# CW308T_K24_Misc.net
KiCad netlist of a schematic drawn in Altium Designer
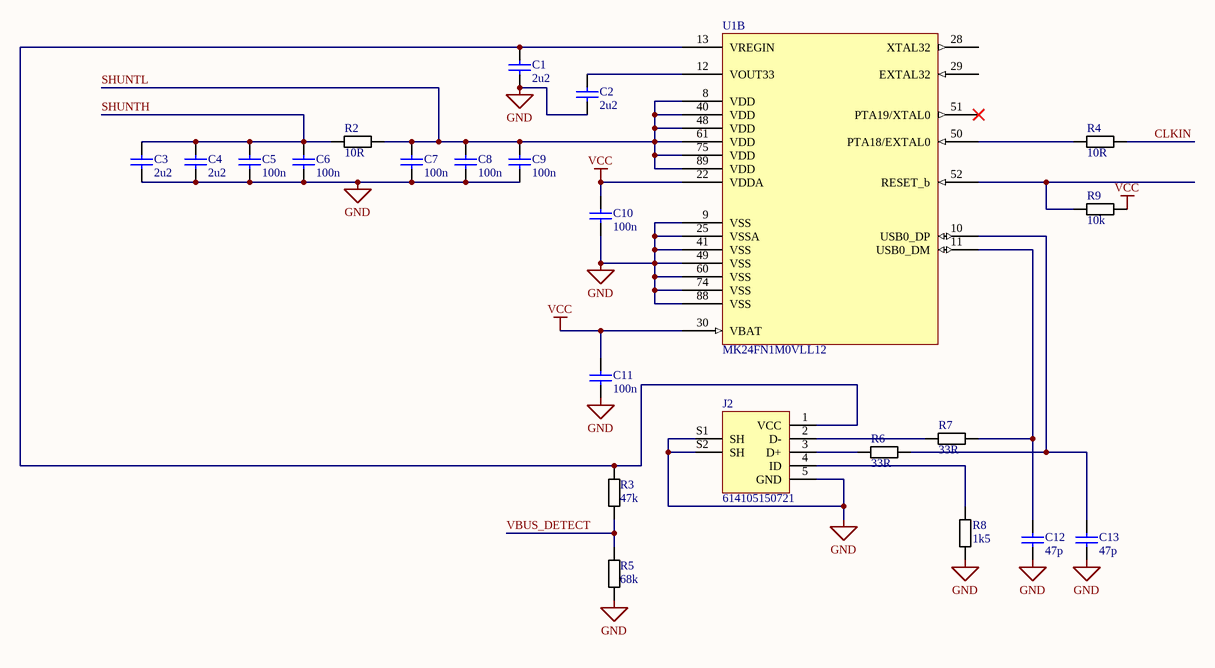
[diagram p0: CW308T_K24_Misc.SchDoc]

(export (version "E")
  (design (tool "Eeschema 10.0.6"))
  (components
    (comp (ref "C1")
      (value "2u2")
      (footprint "CAPC0603_M")
      (description "2u2, 0603")
      (fields (field (name "PART NUMBER") "CCHIP-2u2-0603"))
      (libsource (lib "NewAE_AltiumLib") (part "CAP"))
    )
    (comp (ref "C2")
      (value "2u2")
      (footprint "CAPC0603_M")
      (description "2u2, 0603")
      (fields (field (name "PART NUMBER") "CCHIP-2u2-0603"))
      (libsource (lib "NewAE_AltiumLib") (part "CAP"))
    )
    (comp (ref "C3")
      (value "2u2")
      (footprint "CAPC0603_M")
      (description "2u2, 0603")
      (fields (field (name "PART NUMBER") "CCHIP-2u2-0603"))
      (libsource (lib "NewAE_AltiumLib") (part "CAP"))
    )
    (comp (ref "C4")
      (value "2u2")
      (footprint "CAPC0603_M")
      (description "2u2, 0603")
      (fields (field (name "PART NUMBER") "CCHIP-2u2-0603"))
      (libsource (lib "NewAE_AltiumLib") (part "CAP"))
    )
    (comp (ref "C5")
      (value "100n")
      (footprint "CAPC0603_M")
      (description "100n, 0603")
      (fields (field (name "PART NUMBER") "CCHIP-100n-0603"))
      (libsource (lib "NewAE_AltiumLib") (part "CAP"))
    )
    (comp (ref "C6")
      (value "100n")
      (footprint "CAPC0603_M")
      (description "100n, 0603")
      (fields (field (name "PART NUMBER") "CCHIP-100n-0603"))
      (libsource (lib "NewAE_AltiumLib") (part "CAP"))
    )
    (comp (ref "C7")
      (value "100n")
      (footprint "CAPC0603_M")
      (description "100n, 0603")
      (fields (field (name "PART NUMBER") "CCHIP-100n-0603"))
      (libsource (lib "NewAE_AltiumLib") (part "CAP"))
    )
    (comp (ref "C8")
      (value "100n")
      (footprint "CAPC0603_M")
      (description "100n, 0603")
      (fields (field (name "PART NUMBER") "CCHIP-100n-0603"))
      (libsource (lib "NewAE_AltiumLib") (part "CAP"))
    )
    (comp (ref "C9")
      (value "100n")
      (footprint "CAPC0603_M")
      (description "100n, 0603")
      (fields (field (name "PART NUMBER") "CCHIP-100n-0603"))
      (libsource (lib "NewAE_AltiumLib") (part "CAP"))
    )
    (comp (ref "C10")
      (value "100n")
      (footprint "CAPC0603_M")
      (description "100n, 0603")
      (fields (field (name "PART NUMBER") "CCHIP-100n-0603"))
      (libsource (lib "NewAE_AltiumLib") (part "CAP"))
    )
    (comp (ref "C11")
      (value "100n")
      (footprint "CAPC0603_M")
      (description "100n, 0603")
      (fields (field (name "PART NUMBER") "CCHIP-100n-0603"))
      (libsource (lib "NewAE_AltiumLib") (part "CAP"))
    )
    (comp (ref "C12")
      (value "47p")
      (footprint "CAPC0603_M")
      (description "47p, 0603")
      (fields (field (name "PART NUMBER") "CCHIP-47p-0603"))
      (libsource (lib "NewAE_AltiumLib") (part "CAP"))
    )
    (comp (ref "C13")
      (value "47p")
      (footprint "CAPC0603_M")
      (description "47p, 0603")
      (fields (field (name "PART NUMBER") "CCHIP-47p-0603"))
      (libsource (lib "NewAE_AltiumLib") (part "CAP"))
    )
    (comp (ref "J2")
      (value "614105150721")
      (footprint "614105150721")
      (description "USB, 5-pin, Upright")
      (libsource (lib "NewAE_AltiumLib") (part "USB_5PIN_2SHIELD"))
    )
    (comp (ref "R2")
      (value "10R")
      (footprint "RESC1608X55N")
      (description "10R res, 0603, 1%, 1/10W")
      (fields (field (name "PART NUMBER") "RCHIP-10R-0603") (field (name "TOLERANCE") "1%"))
      (libsource (lib "") (part "RES-EU_1"))
    )
    (comp (ref "R3")
      (value "47k")
      (footprint "RESC1608X55N")
      (description "47k res, 0603, 1%, 1/10W")
      (fields (field (name "PART NUMBER") "RCHIP-47K-0603") (field (name "TOLERANCE") "1%"))
      (libsource (lib "NewAE_AltiumLib") (part "RES-EU"))
    )
    (comp (ref "R4")
      (value "10R")
      (footprint "RESC1608X55N")
      (description "10R res, 0603, 1%, 1/10W")
      (fields (field (name "PART NUMBER") "RCHIP-10R-0603") (field (name "TOLERANCE") "1%"))
      (libsource (lib "") (part "RES-EU_1"))
    )
    (comp (ref "R5")
      (value "68k")
      (footprint "RESC1608X55N")
      (description "68k res, 0603, 1%, 1/10W")
      (fields (field (name "PART NUMBER") "RCHIP-68K-0603") (field (name "TOLERANCE") "1%"))
      (libsource (lib "NewAE_AltiumLib") (part "RES-EU"))
    )
    (comp (ref "R6")
      (value "33R")
      (footprint "RESC1608X55N")
      (description "33R res, 0603, 1%, 1/10W")
      (fields (field (name "PART NUMBER") "RCHIP-33R-0603") (field (name "TOLERANCE") "1%"))
      (libsource (lib "") (part "RES-EU_2"))
    )
    (comp (ref "R7")
      (value "33R")
      (footprint "RESC1608X55N")
      (description "33R res, 0603, 1%, 1/10W")
      (fields (field (name "PART NUMBER") "RCHIP-33R-0603") (field (name "TOLERANCE") "1%"))
      (libsource (lib "") (part "RES-EU_1"))
    )
    (comp (ref "R8")
      (value "1k5")
      (footprint "RESC1608X55N")
      (description "1k5 res, 0603, 1%, 1/10W")
      (fields (field (name "PART NUMBER") "RCHIP-1K5-0603") (field (name "TOLERANCE") "1%"))
      (libsource (lib "NewAE_AltiumLib") (part "RES-EU"))
    )
    (comp (ref "R9")
      (value "10k")
      (footprint "RESC1608X55N")
      (description "10k res, 0603, 1%, 1/10W")
      (fields (field (name "PART NUMBER") "RCHIP-10K-0603") (field (name "TOLERANCE") "1%"))
      (libsource (lib "") (part "RES-EU_1"))
    )
    (comp (ref "U1")
      (value "MK24FN1M0VLL12")
      (footprint "SQFP50P1600X1600X170-100N")
      (libsource (lib "NewAE_AltiumLib") (part "MK24FN1M0VLL12"))
    )
  )
  (nets
    (net (code "1") (name "/CLKIN") (class "Default")
      (node (ref "R4") (pin "2") (pinfunction "2_2") (pintype "passive"))
    )
    (net (code "2") (name "/SHUNTH") (class "Default")
      (node (ref "C3") (pin "1") (pinfunction "1_1") (pintype "passive"))
      (node (ref "C4") (pin "1") (pinfunction "1_1") (pintype "passive"))
      (node (ref "C5") (pin "1") (pinfunction "1_1") (pintype "passive"))
      (node (ref "C6") (pin "1") (pinfunction "1_1") (pintype "passive"))
      (node (ref "R2") (pin "1") (pinfunction "1_1") (pintype "passive"))
    )
    (net (code "3") (name "/SHUNTL") (class "Default")
      (node (ref "C7") (pin "1") (pinfunction "1_1") (pintype "passive"))
      (node (ref "C8") (pin "1") (pinfunction "1_1") (pintype "passive"))
      (node (ref "C9") (pin "1") (pinfunction "1_1") (pintype "passive"))
      (node (ref "R2") (pin "2") (pinfunction "2_2") (pintype "passive"))
      (node (ref "U1") (pin "40") (pinfunction "VDD_40") (pintype "power_in"))
      (node (ref "U1") (pin "48") (pinfunction "VDD_48") (pintype "power_in"))
      (node (ref "U1") (pin "61") (pinfunction "VDD_61") (pintype "power_in"))
      (node (ref "U1") (pin "75") (pinfunction "VDD_75") (pintype "power_in"))
      (node (ref "U1") (pin "8") (pinfunction "VDD_8") (pintype "power_in"))
      (node (ref "U1") (pin "89") (pinfunction "VDD_89") (pintype "power_in"))
    )
    (net (code "4") (name "/VBUS_DETECT") (class "Default")
      (node (ref "R3") (pin "2") (pinfunction "2_2") (pintype "passive"))
      (node (ref "R5") (pin "1") (pinfunction "1_1") (pintype "passive"))
    )
    (net (code "5") (name "GND") (class "Default")
      (node (ref "C1") (pin "2") (pinfunction "2_2") (pintype "passive"))
      (node (ref "C10") (pin "2") (pinfunction "2_2") (pintype "passive"))
      (node (ref "C11") (pin "2") (pinfunction "2_2") (pintype "passive"))
      (node (ref "C12") (pin "2") (pinfunction "2_2") (pintype "passive"))
      (node (ref "C13") (pin "2") (pinfunction "2_2") (pintype "passive"))
      (node (ref "C2") (pin "2") (pinfunction "2_2") (pintype "passive"))
      (node (ref "C3") (pin "2") (pinfunction "2_2") (pintype "passive"))
      (node (ref "C4") (pin "2") (pinfunction "2_2") (pintype "passive"))
      (node (ref "C5") (pin "2") (pinfunction "2_2") (pintype "passive"))
      (node (ref "C6") (pin "2") (pinfunction "2_2") (pintype "passive"))
      (node (ref "C7") (pin "2") (pinfunction "2_2") (pintype "passive"))
      (node (ref "C8") (pin "2") (pinfunction "2_2") (pintype "passive"))
      (node (ref "C9") (pin "2") (pinfunction "2_2") (pintype "passive"))
      (node (ref "J2") (pin "5") (pinfunction "GND_5") (pintype "power_in"))
      (node (ref "J2") (pin "S1") (pinfunction "SH_S1") (pintype "passive"))
      (node (ref "J2") (pin "S2") (pinfunction "SH_S2") (pintype "passive"))
      (node (ref "R5") (pin "2") (pinfunction "2_2") (pintype "passive"))
      (node (ref "R8") (pin "2") (pinfunction "2_2") (pintype "passive"))
      (node (ref "U1") (pin "25") (pinfunction "VSSA_25") (pintype "power_in"))
      (node (ref "U1") (pin "41") (pinfunction "VSS_41") (pintype "power_in"))
      (node (ref "U1") (pin "49") (pinfunction "VSS_49") (pintype "power_in"))
      (node (ref "U1") (pin "60") (pinfunction "VSS_60") (pintype "power_in"))
      (node (ref "U1") (pin "74") (pinfunction "VSS_74") (pintype "power_in"))
      (node (ref "U1") (pin "88") (pinfunction "VSS_88") (pintype "power_in"))
      (node (ref "U1") (pin "9") (pinfunction "VSS_9") (pintype "power_in"))
    )
    (net (code "6") (name "Net-(J2-D+)") (class "Default")
      (node (ref "J2") (pin "3") (pinfunction "D+_3") (pintype "passive"))
      (node (ref "R6") (pin "2") (pinfunction "2_2") (pintype "passive"))
    )
    (net (code "7") (name "Net-(J2-D-)") (class "Default")
      (node (ref "J2") (pin "2") (pinfunction "D-_2") (pintype "passive"))
      (node (ref "R7") (pin "1") (pinfunction "1_1") (pintype "passive"))
    )
    (net (code "8") (name "Net-(J2-ID)") (class "Default")
      (node (ref "J2") (pin "4") (pinfunction "ID_4") (pintype "power_in"))
      (node (ref "R8") (pin "1") (pinfunction "1_1") (pintype "passive"))
    )
    (net (code "9") (name "Net-(J2-VCC)") (class "Default")
      (node (ref "C1") (pin "1") (pinfunction "1_1") (pintype "passive"))
      (node (ref "J2") (pin "1") (pinfunction "VCC_1") (pintype "passive"))
      (node (ref "R3") (pin "1") (pinfunction "1_1") (pintype "passive"))
      (node (ref "U1") (pin "13") (pinfunction "VREGIN_13") (pintype "power_in"))
    )
    (net (code "10") (name "Net-(U1B-PTA18{slash}EXTAL0)") (class "Default")
      (node (ref "R4") (pin "1") (pinfunction "1_1") (pintype "passive"))
      (node (ref "U1") (pin "50") (pinfunction "PTA18/EXTAL0_50") (pintype "input"))
    )
    (net (code "11") (name "Net-(U1B-RESET_b)") (class "Default")
      (node (ref "R9") (pin "1") (pinfunction "1_1") (pintype "passive"))
      (node (ref "U1") (pin "52") (pinfunction "RESET_b_52") (pintype "input"))
    )
    (net (code "12") (name "Net-(U1B-USB0_DM)") (class "Default")
      (node (ref "C12") (pin "1") (pinfunction "1_1") (pintype "passive"))
      (node (ref "R7") (pin "2") (pinfunction "2_2") (pintype "passive"))
      (node (ref "U1") (pin "11") (pinfunction "USB0_DM_11") (pintype "bidirectional"))
    )
    (net (code "13") (name "Net-(U1B-USB0_DP)") (class "Default")
      (node (ref "C13") (pin "1") (pinfunction "1_1") (pintype "passive"))
      (node (ref "R6") (pin "1") (pinfunction "1_1") (pintype "passive"))
      (node (ref "U1") (pin "10") (pinfunction "USB0_DP_10") (pintype "bidirectional"))
    )
    (net (code "14") (name "Net-(U1B-VOUT33)") (class "Default")
      (node (ref "C2") (pin "1") (pinfunction "1_1") (pintype "passive"))
      (node (ref "U1") (pin "12") (pinfunction "VOUT33_12") (pintype "power_in"))
    )
    (net (code "15") (name "VCC") (class "Default")
      (node (ref "C10") (pin "1") (pinfunction "1_1") (pintype "passive"))
      (node (ref "C11") (pin "1") (pinfunction "1_1") (pintype "passive"))
      (node (ref "R9") (pin "2") (pinfunction "2_2") (pintype "passive"))
      (node (ref "U1") (pin "22") (pinfunction "VDDA_22") (pintype "power_in"))
      (node (ref "U1") (pin "30") (pinfunction "VBAT_30") (pintype "input"))
    )
    (net (code "16") (name "unconnected-(U1B-EXTAL32-Pad29)") (class "Default")
      (node (ref "U1") (pin "29") (pinfunction "EXTAL32_29") (pintype "input"))
    )
    (net (code "17") (name "unconnected-(U1B-PTA19{slash}XTAL0-Pad51)") (class "Default")
      (node (ref "U1") (pin "51") (pinfunction "PTA19/XTAL0_51") (pintype "output+no_connect"))
    )
    (net (code "18") (name "unconnected-(U1B-XTAL32-Pad28)") (class "Default")
      (node (ref "U1") (pin "28") (pinfunction "XTAL32_28") (pintype "output"))
    )
  )
)
